# pPsch.net
KiCad netlist of a schematic drawn in Altium Designer
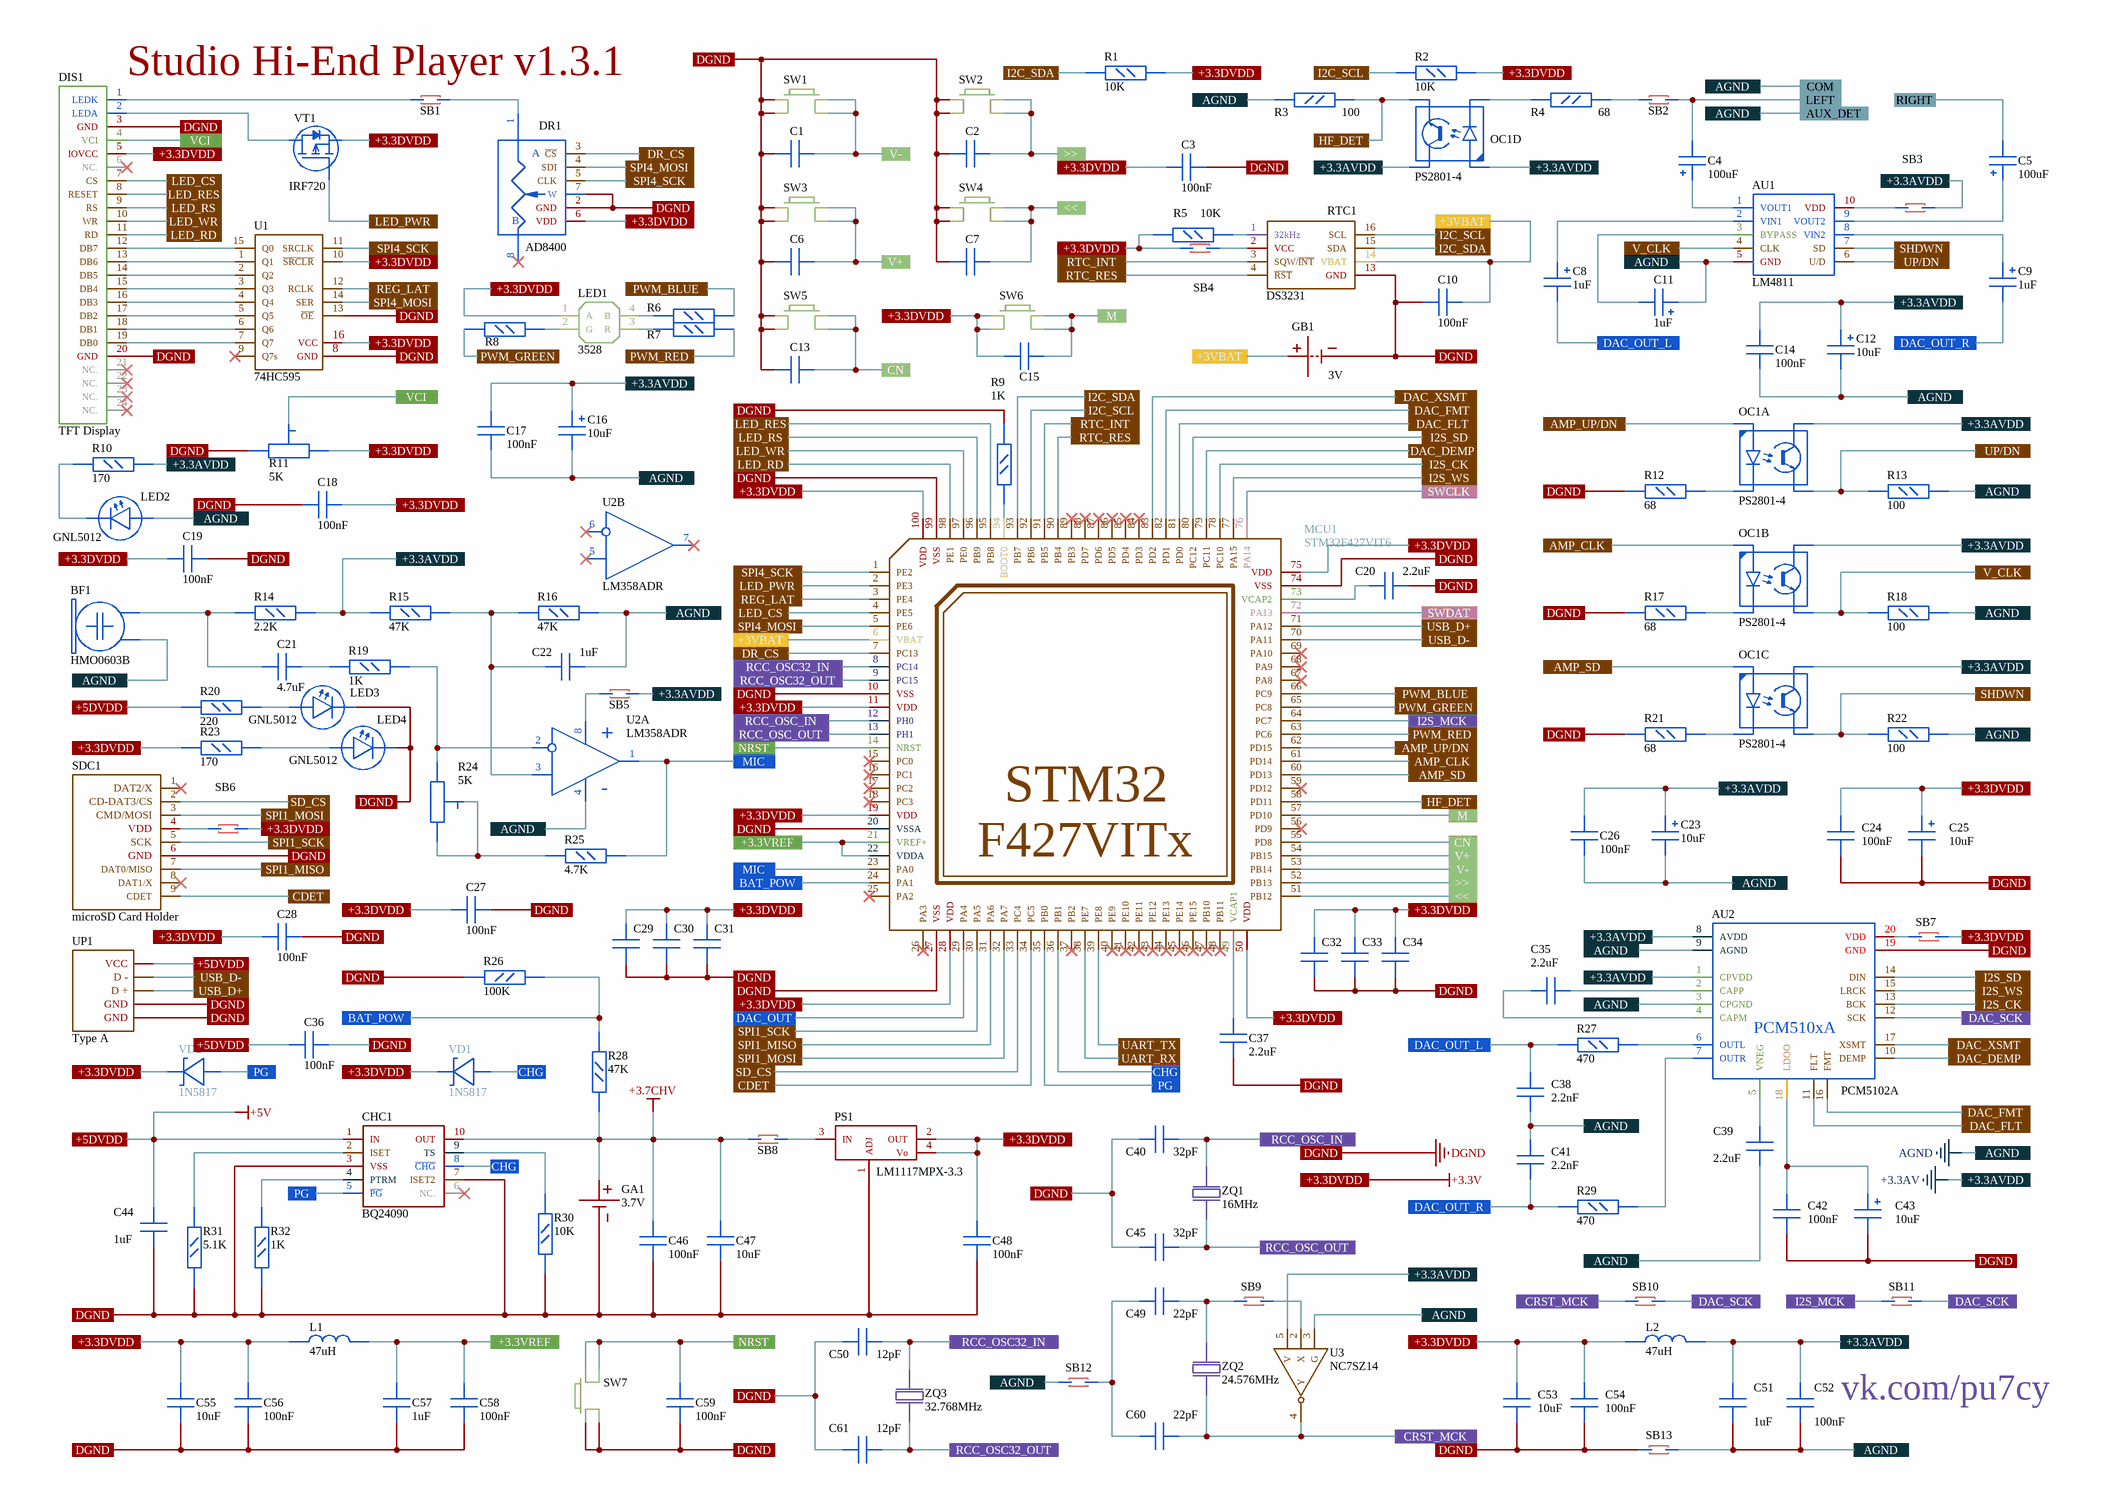
[diagram p0: pPsch.SchDoc]

(export (version "E")
  (design (tool "Eeschema 10.0.6"))
  (components
    (comp (ref "AU1")
      (value "LM4811")
      (footprint "HVSSOP10")
      (libsource (lib "AudioStonesLib_Col") (part "LM4811"))
    )
    (comp (ref "AU2")
      (value "PCM5102A")
      (footprint "TSSOP20")
      (libsource (lib "AudioStonesLib_Col") (part "PCM510xA"))
    )
    (comp (ref "BF1")
      (value "HMO0603B")
      (footprint "ACCUM")
      (libsource (lib "CustomMillLib_Col") (part "Microphone"))
    )
    (comp (ref "C1") (value "100nF") (footprint "C0603") (libsource (lib "CustomMillLib_Col") (part "Cap")))
    (comp (ref "C2") (value "100nF") (footprint "C0603") (libsource (lib "CustomMillLib_Col") (part "Cap")))
    (comp (ref "C3") (value "100nF") (footprint "C0603") (libsource (lib "CustomMillLib_Col") (part "Cap")))
    (comp (ref "C4")
      (value "100uF")
      (footprint "CAP_TAN-C")
      (libsource (lib "CustomMillLib_Col") (part "Cap_Pol"))
    )
    (comp (ref "C5")
      (value "100uF")
      (footprint "CAP_TAN-C")
      (libsource (lib "CustomMillLib_Col") (part "Cap_Pol"))
    )
    (comp (ref "C6") (value "100nF") (footprint "C0603") (libsource (lib "CustomMillLib_Col") (part "Cap")))
    (comp (ref "C7") (value "100nF") (footprint "C0603") (libsource (lib "CustomMillLib_Col") (part "Cap")))
    (comp (ref "C8")
      (value "1uF")
      (footprint "CAP_TAN-A")
      (libsource (lib "CustomMillLib_Col") (part "Cap_Pol"))
    )
    (comp (ref "C9")
      (value "1uF")
      (footprint "CAP_TAN-A")
      (libsource (lib "CustomMillLib_Col") (part "Cap_Pol"))
    )
    (comp (ref "C10") (value "100nF") (footprint "C0603") (libsource (lib "CustomMillLib_Col") (part "Cap")))
    (comp (ref "C11")
      (value "1uF")
      (footprint "CAP_TAN-A")
      (libsource (lib "CustomMillLib_Col") (part "Cap_Pol"))
    )
    (comp (ref "C12")
      (value "10uF")
      (footprint "CAP_TAN-A")
      (libsource (lib "CustomMillLib_Col") (part "Cap_Pol"))
    )
    (comp (ref "C13") (value "100nF") (footprint "C0603") (libsource (lib "CustomMillLib_Col") (part "Cap")))
    (comp (ref "C14") (value "100nF") (footprint "C0603") (libsource (lib "CustomMillLib_Col") (part "Cap")))
    (comp (ref "C15") (value "100nF") (footprint "C0603") (libsource (lib "CustomMillLib_Col") (part "Cap")))
    (comp (ref "C16")
      (value "10uF")
      (footprint "CAP_TAN-A")
      (libsource (lib "CustomMillLib_Col") (part "Cap_Pol"))
    )
    (comp (ref "C17") (value "100nF") (footprint "C0603") (libsource (lib "CustomMillLib_Col") (part "Cap")))
    (comp (ref "C18") (value "100nF") (footprint "C0603") (libsource (lib "CustomMillLib_Col") (part "Cap")))
    (comp (ref "C19") (value "100nF") (footprint "C0603") (libsource (lib "CustomMillLib_Col") (part "Cap")))
    (comp (ref "C20") (value "2.2uF") (footprint "C0805") (libsource (lib "CustomMillLib_Col") (part "Cap")))
    (comp (ref "C21") (value "4.7uF") (footprint "C0805") (libsource (lib "CustomMillLib_Col") (part "Cap")))
    (comp (ref "C22") (value "1uF") (footprint "C0805") (libsource (lib "CustomMillLib_Col") (part "Cap")))
    (comp (ref "C23")
      (value "10uF")
      (footprint "CAP_TAN-A")
      (libsource (lib "CustomMillLib_Col") (part "Cap_Pol"))
    )
    (comp (ref "C24") (value "100nF") (footprint "C0603") (libsource (lib "CustomMillLib_Col") (part "Cap")))
    (comp (ref "C25")
      (value "10uF")
      (footprint "CAP_TAN-A")
      (libsource (lib "CustomMillLib_Col") (part "Cap_Pol"))
    )
    (comp (ref "C26") (value "100nF") (footprint "C0603") (libsource (lib "CustomMillLib_Col") (part "Cap")))
    (comp (ref "C27") (value "100nF") (footprint "C0603") (libsource (lib "CustomMillLib_Col") (part "Cap")))
    (comp (ref "C28") (value "100nF") (footprint "C0603") (libsource (lib "CustomMillLib_Col") (part "Cap")))
    (comp (ref "C29") (value "100nF") (footprint "C0603") (libsource (lib "CustomMillLib_Col") (part "Cap")))
    (comp (ref "C30") (value "100nF") (footprint "C0603") (libsource (lib "CustomMillLib_Col") (part "Cap")))
    (comp (ref "C31") (value "100nF") (footprint "C0603") (libsource (lib "CustomMillLib_Col") (part "Cap")))
    (comp (ref "C32") (value "100nF") (footprint "C0603") (libsource (lib "CustomMillLib_Col") (part "Cap")))
    (comp (ref "C33") (value "100nF") (footprint "C0603") (libsource (lib "CustomMillLib_Col") (part "Cap")))
    (comp (ref "C34") (value "100nF") (footprint "C0603") (libsource (lib "CustomMillLib_Col") (part "Cap")))
    (comp (ref "C35") (value "2.2uF") (footprint "C0805") (libsource (lib "CustomMillLib_Col") (part "Cap")))
    (comp (ref "C36") (value "100nF") (footprint "C0603") (libsource (lib "CustomMillLib_Col") (part "Cap")))
    (comp (ref "C37") (value "2.2uF") (footprint "C0805") (libsource (lib "CustomMillLib_Col") (part "Cap")))
    (comp (ref "C38") (value "2.2nF") (footprint "C0603") (libsource (lib "CustomMillLib_Col") (part "Cap")))
    (comp (ref "C39") (value "2.2uF") (footprint "C0805") (libsource (lib "CustomMillLib_Col") (part "Cap")))
    (comp (ref "C40") (value "32pF") (footprint "C0402") (libsource (lib "CustomMillLib_Col") (part "Cap")))
    (comp (ref "C41") (value "2.2nF") (footprint "C0603") (libsource (lib "CustomMillLib_Col") (part "Cap")))
    (comp (ref "C42") (value "100nF") (footprint "C0603") (libsource (lib "CustomMillLib_Col") (part "Cap")))
    (comp (ref "C43")
      (value "10uF")
      (footprint "CAP_TAN-A")
      (libsource (lib "CustomMillLib_Col") (part "Cap_Pol"))
    )
    (comp (ref "C44") (value "1uF") (footprint "C0805") (libsource (lib "CustomMillLib_Col") (part "Cap")))
    (comp (ref "C45") (value "32pF") (footprint "C0402") (libsource (lib "CustomMillLib_Col") (part "Cap")))
    (comp (ref "C46") (value "100nF") (footprint "C0603") (libsource (lib "CustomMillLib_Col") (part "Cap")))
    (comp (ref "C47") (value "10uF") (footprint "C0805") (libsource (lib "CustomMillLib_Col") (part "Cap")))
    (comp (ref "C48") (value "100nF") (footprint "C0603") (libsource (lib "CustomMillLib_Col") (part "Cap")))
    (comp (ref "C49") (value "22pF") (footprint "C0402") (libsource (lib "CustomMillLib_Col") (part "Cap")))
    (comp (ref "C50") (value "12pF") (footprint "C0402") (libsource (lib "CustomMillLib_Col") (part "Cap")))
    (comp (ref "C51") (value "1uF") (footprint "C0805") (libsource (lib "CustomMillLib_Col") (part "Cap")))
    (comp (ref "C52") (value "100nF") (footprint "C0603") (libsource (lib "CustomMillLib_Col") (part "Cap")))
    (comp (ref "C53") (value "10uF") (footprint "C0805") (libsource (lib "CustomMillLib_Col") (part "Cap")))
    (comp (ref "C54") (value "100nF") (footprint "C0603") (libsource (lib "CustomMillLib_Col") (part "Cap")))
    (comp (ref "C55") (value "10uF") (footprint "C0805") (libsource (lib "CustomMillLib_Col") (part "Cap")))
    (comp (ref "C56") (value "100nF") (footprint "C0603") (libsource (lib "CustomMillLib_Col") (part "Cap")))
    (comp (ref "C57") (value "1uF") (footprint "C0805") (libsource (lib "CustomMillLib_Col") (part "Cap")))
    (comp (ref "C58") (value "100nF") (footprint "C0603") (libsource (lib "CustomMillLib_Col") (part "Cap")))
    (comp (ref "C59") (value "100nF") (footprint "C0603") (libsource (lib "CustomMillLib_Col") (part "Cap")))
    (comp (ref "C60") (value "22pF") (footprint "C0402") (libsource (lib "CustomMillLib_Col") (part "Cap")))
    (comp (ref "C61") (value "12pF") (footprint "C0402") (libsource (lib "CustomMillLib_Col") (part "Cap")))
    (comp (ref "CHC1")
      (value "BQ24090")
      (footprint "HVSSOP10")
      (libsource (lib "PowerSupplies_Col") (part "BQ24090"))
    )
    (comp (ref "DIS1")
      (value "TFT Display")
      (footprint "FPC-24")
      (libsource (lib "OtherEquipmentLib_Col") (part "TFT RGB (ST7789/ILI9341)"))
    )
    (comp (ref "DR1")
      (value "AD8400")
      (footprint "SOIC8")
      (libsource (lib "DigitalUnits_Col") (part "AD8400"))
    )
    (comp (ref "GA1")
      (value "3.7V")
      (footprint "ACCUM")
      (libsource (lib "PowerSupplies_Col") (part "Accumulator"))
    )
    (comp (ref "GB1")
      (value "3V")
      (footprint "CR1616-SMD")
      (libsource (lib "PowerSupplies_Col") (part "Battery"))
    )
    (comp (ref "L1")
      (value "47uH")
      (footprint "L0805")
      (libsource (lib "CustomMillLib_Col") (part "Inductor"))
    )
    (comp (ref "L2")
      (value "47uH")
      (footprint "L0805")
      (libsource (lib "CustomMillLib_Col") (part "Inductor"))
    )
    (comp (ref "LED1")
      (value "3528")
      (footprint "LED-3528")
      (libsource (lib "CustomMillLib_Col") (part "LED-RGB"))
    )
    (comp (ref "LED2")
      (value "GNL5012")
      (footprint "LED0603")
      (libsource (lib "CustomMillLib_Col") (part "LED"))
    )
    (comp (ref "LED3")
      (value "GNL5012")
      (footprint "LED0603")
      (libsource (lib "CustomMillLib_Col") (part "LED"))
    )
    (comp (ref "LED4")
      (value "GNL5012")
      (footprint "LED0603")
      (libsource (lib "CustomMillLib_Col") (part "LED"))
    )
    (comp (ref "MCU1")
      (value "STM32F427VIT6")
      (footprint "LQFP100")
      (libsource (lib "STM32Lib_Col") (part "STM32F427VITx"))
    )
    (comp (ref "OC1")
      (value "PS2801-4")
      (footprint "SSOP16")
      (libsource (lib "CustomMillLib_Col") (part "PS2801-4"))
    )
    (comp (ref "PS1")
      (value "LM1117MPX-3.3")
      (footprint "SOT-223")
      (libsource (lib "PowerSupplies_Col") (part "LM1117"))
    )
    (comp (ref "R1") (value "10K") (footprint "R0603") (libsource (lib "CustomMillLib_Col") (part "Res")))
    (comp (ref "R2") (value "10K") (footprint "R0603") (libsource (lib "CustomMillLib_Col") (part "Res")))
    (comp (ref "R3") (value "100") (footprint "R0805") (libsource (lib "CustomMillLib_Col") (part "Res")))
    (comp (ref "R4") (value "68") (footprint "R0805") (libsource (lib "CustomMillLib_Col") (part "Res")))
    (comp (ref "R5") (value "10K") (footprint "R0603") (libsource (lib "CustomMillLib_Col") (part "Res")))
    (comp (ref "R6") (value "220") (footprint "R0603") (libsource (lib "CustomMillLib_Col") (part "Res")))
    (comp (ref "R7") (value "220") (footprint "R0603") (libsource (lib "CustomMillLib_Col") (part "Res")))
    (comp (ref "R8") (value "220") (footprint "R0603") (libsource (lib "CustomMillLib_Col") (part "Res")))
    (comp (ref "R9") (value "1K") (footprint "R0603") (libsource (lib "CustomMillLib_Col") (part "Res")))
    (comp (ref "R10") (value "170") (footprint "R0805") (libsource (lib "CustomMillLib_Col") (part "Res")))
    (comp (ref "R11") (value "5K") (footprint "EVM3") (libsource (lib "") (part "Res Adj_1")))
    (comp (ref "R12") (value "68") (footprint "R0805") (libsource (lib "CustomMillLib_Col") (part "Res")))
    (comp (ref "R13") (value "100") (footprint "R0805") (libsource (lib "CustomMillLib_Col") (part "Res")))
    (comp (ref "R14") (value "2.2K") (footprint "R0603") (libsource (lib "CustomMillLib_Col") (part "Res")))
    (comp (ref "R15") (value "47K") (footprint "R0603") (libsource (lib "CustomMillLib_Col") (part "Res")))
    (comp (ref "R16") (value "47K") (footprint "R0603") (libsource (lib "CustomMillLib_Col") (part "Res")))
    (comp (ref "R17") (value "68") (footprint "R0805") (libsource (lib "CustomMillLib_Col") (part "Res")))
    (comp (ref "R18") (value "100") (footprint "R0805") (libsource (lib "CustomMillLib_Col") (part "Res")))
    (comp (ref "R19") (value "1K") (footprint "R0603") (libsource (lib "CustomMillLib_Col") (part "Res")))
    (comp (ref "R20") (value "220") (footprint "R0805") (libsource (lib "CustomMillLib_Col") (part "Res")))
    (comp (ref "R21") (value "68") (footprint "R0805") (libsource (lib "CustomMillLib_Col") (part "Res")))
    (comp (ref "R22") (value "100") (footprint "R0805") (libsource (lib "CustomMillLib_Col") (part "Res")))
    (comp (ref "R23") (value "170") (footprint "R0805") (libsource (lib "CustomMillLib_Col") (part "Res")))
    (comp (ref "R24") (value "5K") (footprint "EVM3") (libsource (lib "CustomMillLib_Col") (part "Res Adj")))
    (comp (ref "R25") (value "4.7K") (footprint "R0603") (libsource (lib "CustomMillLib_Col") (part "Res")))
    (comp (ref "R26") (value "100K") (footprint "R0603") (libsource (lib "CustomMillLib_Col") (part "Res")))
    (comp (ref "R27") (value "470") (footprint "R0603") (libsource (lib "CustomMillLib_Col") (part "Res")))
    (comp (ref "R28") (value "47K") (footprint "R0603") (libsource (lib "CustomMillLib_Col") (part "Res")))
    (comp (ref "R29") (value "470") (footprint "R0603") (libsource (lib "CustomMillLib_Col") (part "Res")))
    (comp (ref "R30") (value "10K") (footprint "R0603") (libsource (lib "CustomMillLib_Col") (part "Res")))
    (comp (ref "R31") (value "5.1K") (footprint "R0603") (libsource (lib "CustomMillLib_Col") (part "Res")))
    (comp (ref "R32") (value "1K") (footprint "R0603") (libsource (lib "CustomMillLib_Col") (part "Res")))
    (comp (ref "RTC1")
      (value "DS3231")
      (footprint "SOP16")
      (libsource (lib "DigitalUnits_Col") (part "DS3231"))
    )
    (comp (ref "SB1")
      (value "Soldier Bridge")
      (footprint "SOLDBR")
      (libsource (lib "CustomMillLib_Col") (part "Soldier Bridge"))
    )
    (comp (ref "SB2")
      (value "Soldier Bridge")
      (footprint "SOLDBR")
      (libsource (lib "CustomMillLib_Col") (part "Soldier Bridge"))
    )
    (comp (ref "SB3")
      (value "Soldier Bridge")
      (footprint "SOLDBR")
      (libsource (lib "CustomMillLib_Col") (part "Soldier Bridge"))
    )
    (comp (ref "SB4")
      (value "Soldier Bridge")
      (footprint "SOLDBR")
      (libsource (lib "CustomMillLib_Col") (part "Soldier Bridge"))
    )
    (comp (ref "SB5")
      (value "Soldier Bridge")
      (footprint "SOLDBR")
      (libsource (lib "CustomMillLib_Col") (part "Soldier Bridge"))
    )
    (comp (ref "SB6")
      (value "Soldier Bridge")
      (footprint "SOLDBR")
      (libsource (lib "CustomMillLib_Col") (part "Soldier Bridge"))
    )
    (comp (ref "SB7")
      (value "Soldier Bridge")
      (footprint "SOLDBR")
      (libsource (lib "CustomMillLib_Col") (part "Soldier Bridge"))
    )
    (comp (ref "SB8")
      (value "Soldier Bridge")
      (footprint "SOLDBR")
      (libsource (lib "CustomMillLib_Col") (part "Soldier Bridge"))
    )
    (comp (ref "SB9")
      (value "Soldier Bridge")
      (footprint "SOLDBR")
      (libsource (lib "CustomMillLib_Col") (part "Soldier Bridge"))
    )
    (comp (ref "SB10")
      (value "Soldier Bridge")
      (footprint "SOLDBR")
      (libsource (lib "CustomMillLib_Col") (part "Soldier Bridge"))
    )
    (comp (ref "SB11")
      (value "Soldier Bridge")
      (footprint "SOLDBR")
      (libsource (lib "CustomMillLib_Col") (part "Soldier Bridge"))
    )
    (comp (ref "SB12")
      (value "Soldier Bridge")
      (footprint "SOLDBR")
      (libsource (lib "CustomMillLib_Col") (part "Soldier Bridge"))
    )
    (comp (ref "SB13")
      (value "Soldier Bridge")
      (footprint "SOLDBR")
      (libsource (lib "CustomMillLib_Col") (part "Soldier Bridge"))
    )
    (comp (ref "SDC1")
      (value "microSD Card Holder")
      (footprint "SDCARD-MICRO")
      (libsource (lib "OtherEquipmentLib_Col") (part "SPI_Card_Reader"))
    )
    (comp (ref "SW1")
      (value "KLS7-TS6601")
      (footprint "BUT-SMD-6X6-8X6.2")
      (libsource (lib "CustomMillLib_Col") (part "Button_2"))
    )
    (comp (ref "SW2")
      (value "KLS7-TS6601")
      (footprint "BUT-SMD-6X6-8X6.2")
      (libsource (lib "CustomMillLib_Col") (part "Button_2"))
    )
    (comp (ref "SW3")
      (value "KLS7-TS6601")
      (footprint "BUT-SMD-6X6-8X6.2")
      (libsource (lib "CustomMillLib_Col") (part "Button_2"))
    )
    (comp (ref "SW4")
      (value "KLS7-TS6601")
      (footprint "BUT-SMD-6X6-8X6.2")
      (libsource (lib "CustomMillLib_Col") (part "Button_2"))
    )
    (comp (ref "SW5")
      (value "KLS7-TS6601")
      (footprint "BUT-SMD-6X6-8X6.2")
      (libsource (lib "CustomMillLib_Col") (part "Button_2"))
    )
    (comp (ref "SW6")
      (value "KLS7-TS6601")
      (footprint "BUT-SMD-3X4-C")
      (libsource (lib "CustomMillLib_Col") (part "Button_2"))
    )
    (comp (ref "SW7")
      (value "KLS7-TS6601")
      (footprint "BUT-SMD-6X6-8X6.2")
      (libsource (lib "CustomMillLib_Col") (part "Button_2"))
    )
    (comp (ref "U1")
      (value "74HC595")
      (footprint "TSSOP16")
      (libsource (lib "DigitalUnits_Col") (part "74HC595 (REG)"))
    )
    (comp (ref "U2")
      (value "LM358ADR")
      (footprint "SOIC8")
      (libsource (lib "CustomMillLib_Col") (part "LM358"))
    )
    (comp (ref "U3")
      (value "NC7SZ14")
      (footprint "SOT23-5")
      (libsource (lib "DigitalUnits_Col") (part "NOT"))
    )
    (comp (ref "UP1")
      (value "Type A")
      (footprint "USB-MICRO-F")
      (libsource (lib "OtherEquipmentLib_Col") (part "USB"))
    )
    (comp (ref "VD1")
      (value "1N5817")
      (footprint "AXIAL10D-TR")
      (libsource (lib "CustomMillLib_Col") (part "Schottky"))
    )
    (comp (ref "VD2")
      (value "1N5817")
      (footprint "AXIAL10D-TR")
      (libsource (lib "CustomMillLib_Col") (part "Schottky"))
    )
    (comp (ref "VT1")
      (value "IRF720")
      (footprint "TO-220V")
      (libsource (lib "CustomMillLib_Col") (part "MOSFET-P"))
    )
    (comp (ref "ZQ1")
      (value "16MHz")
      (footprint "CRYSTALL-SMD")
      (libsource (lib "CustomMillLib_Col") (part "Crystall"))
    )
    (comp (ref "ZQ2")
      (value "24.576MHz")
      (footprint "HC-49")
      (libsource (lib "CustomMillLib_Col") (part "Crystall"))
    )
    (comp (ref "ZQ3")
      (value "32.768MHz")
      (footprint "NX3215SA")
      (libsource (lib "CustomMillLib_Col") (part "Crystall"))
    )
  )
  (nets
    (net (code "1") (name "+3.3AV") (class "Default")
      (node (ref "AU2") (pin "1") (pinfunction "CPVDD_1") (pintype "passive"))
      (node (ref "AU2") (pin "8") (pinfunction "AVDD_8") (pintype "passive"))
      (node (ref "C12") (pin "1") (pinfunction "61_1") (pintype "passive"))
      (node (ref "C14") (pin "2") (pinfunction "62_2") (pintype "passive"))
      (node (ref "C16") (pin "1") (pinfunction "61_1") (pintype "passive"))
      (node (ref "C17") (pin "2") (pinfunction "62_2") (pintype "passive"))
      (node (ref "C23") (pin "1") (pinfunction "61_1") (pintype "passive"))
      (node (ref "C26") (pin "2") (pinfunction "62_2") (pintype "passive"))
      (node (ref "C51") (pin "2") (pinfunction "62_2") (pintype "passive"))
      (node (ref "C52") (pin "2") (pinfunction "62_2") (pintype "passive"))
      (node (ref "L2") (pin "2") (pinfunction "4_2") (pintype "passive"))
      (node (ref "OC1") (pin "10") (pinfunction "4_10") (pintype "passive"))
      (node (ref "OC1") (pin "12") (pinfunction "4_12") (pintype "passive"))
      (node (ref "OC1") (pin "14") (pinfunction "4_14") (pintype "passive"))
      (node (ref "OC1") (pin "16") (pinfunction "4_16") (pintype "passive"))
      (node (ref "OC1") (pin "7") (pinfunction "1_7") (pintype "passive"))
      (node (ref "R10") (pin "2") (pinfunction "2_2") (pintype "passive"))
      (node (ref "R14") (pin "2") (pinfunction "2_2") (pintype "passive"))
      (node (ref "R15") (pin "2") (pinfunction "2_2") (pintype "passive"))
      (node (ref "SB3") (pin "2") (pintype "passive"))
      (node (ref "SB5") (pin "2") (pintype "passive"))
      (node (ref "U3") (pin "5") (pinfunction "V_5") (pintype "passive"))
    )
    (net (code "2") (name "+3.3V") (class "Default")
      (node (ref "C15") (pin "1") (pinfunction "61_1") (pintype "passive"))
      (node (ref "C18") (pin "1") (pinfunction "61_1") (pintype "passive"))
      (node (ref "C19") (pin "1") (pinfunction "61_1") (pintype "passive"))
      (node (ref "C24") (pin "2") (pinfunction "62_2") (pintype "passive"))
      (node (ref "C25") (pin "1") (pinfunction "61_1") (pintype "passive"))
      (node (ref "C27") (pin "1") (pinfunction "61_1") (pintype "passive"))
      (node (ref "C28") (pin "1") (pinfunction "61_1") (pintype "passive"))
      (node (ref "C29") (pin "2") (pinfunction "62_2") (pintype "passive"))
      (node (ref "C3") (pin "1") (pinfunction "61_1") (pintype "passive"))
      (node (ref "C30") (pin "2") (pinfunction "62_2") (pintype "passive"))
      (node (ref "C31") (pin "2") (pinfunction "62_2") (pintype "passive"))
      (node (ref "C32") (pin "2") (pinfunction "62_2") (pintype "passive"))
      (node (ref "C33") (pin "2") (pinfunction "62_2") (pintype "passive"))
      (node (ref "C34") (pin "2") (pinfunction "62_2") (pintype "passive"))
      (node (ref "C48") (pin "2") (pinfunction "62_2") (pintype "passive"))
      (node (ref "C53") (pin "2") (pinfunction "62_2") (pintype "passive"))
      (node (ref "C54") (pin "2") (pinfunction "62_2") (pintype "passive"))
      (node (ref "C55") (pin "2") (pinfunction "62_2") (pintype "passive"))
      (node (ref "C56") (pin "2") (pinfunction "62_2") (pintype "passive"))
      (node (ref "DIS1") (pin "5") (pinfunction "IOVCC_5") (pintype "passive"))
      (node (ref "DR1") (pin "6") (pinfunction "VDD_6") (pintype "passive"))
      (node (ref "L1") (pin "1") (pinfunction "3_1") (pintype "passive"))
      (node (ref "L2") (pin "1") (pinfunction "3_1") (pintype "passive"))
      (node (ref "LED1") (pin "1") (pinfunction "A_1") (pintype "passive"))
      (node (ref "MCU1") (pin "100") (pinfunction "VDD_100") (pintype "passive"))
      (node (ref "MCU1") (pin "11") (pinfunction "VDD_11") (pintype "passive"))
      (node (ref "MCU1") (pin "19") (pinfunction "VDD_19") (pintype "passive"))
      (node (ref "MCU1") (pin "28") (pinfunction "VDD_28") (pintype "passive"))
      (node (ref "MCU1") (pin "50") (pinfunction "VDD_50") (pintype "passive"))
      (node (ref "MCU1") (pin "75") (pinfunction "VDD_75") (pintype "passive"))
      (node (ref "PS1") (pin "2") (pinfunction "OUT_2") (pintype "passive"))
      (node (ref "PS1") (pin "4") (pinfunction "Vo_4") (pintype "passive"))
      (node (ref "R1") (pin "2") (pinfunction "2_2") (pintype "passive"))
      (node (ref "R11") (pin "3") (pinfunction "3_3") (pintype "passive"))
      (node (ref "R2") (pin "2") (pinfunction "2_2") (pintype "passive"))
      (node (ref "R23") (pin "1") (pinfunction "2_1") (pintype "passive"))
      (node (ref "R5") (pin "1") (pinfunction "2_1") (pintype "passive"))
      (node (ref "SB4") (pin "1") (pintype "passive"))
      (node (ref "SB6") (pin "2") (pintype "passive"))
      (node (ref "SB7") (pin "2") (pintype "passive"))
      (node (ref "SW6") (pin "1") (pinfunction "Q1_1") (pintype "passive"))
      (node (ref "SW6") (pin "2") (pinfunction "Q1_2") (pintype "passive"))
      (node (ref "U1") (pin "10") (pinfunction "SRCLR_10") (pintype "passive"))
      (node (ref "U1") (pin "16") (pinfunction "VCC_16") (pintype "passive"))
      (node (ref "VD1") (pin "2") (pinfunction "64_2") (pintype "passive"))
      (node (ref "VD2") (pin "2") (pinfunction "64_2") (pintype "passive"))
      (node (ref "VT1") (pin "3") (pinfunction "S_3") (pintype "passive"))
    )
    (net (code "3") (name "+3.7CHV") (class "Default")
      (node (ref "C46") (pin "2") (pinfunction "62_2") (pintype "passive"))
      (node (ref "C47") (pin "2") (pinfunction "62_2") (pintype "passive"))
      (node (ref "CHC1") (pin "10") (pinfunction "OUT_10") (pintype "passive"))
      (node (ref "GA1") (pin "1") (pintype "passive"))
      (node (ref "R28") (pin "2") (pinfunction "2_2") (pintype "passive"))
      (node (ref "SB8") (pin "1") (pintype "passive"))
    )
    (net (code "4") (name "+5V") (class "Default")
      (node (ref "C36") (pin "1") (pinfunction "61_1") (pintype "passive"))
      (node (ref "C44") (pin "2") (pinfunction "62_2") (pintype "passive"))
      (node (ref "CHC1") (pin "1") (pinfunction "IN_1") (pintype "passive"))
      (node (ref "R20") (pin "1") (pinfunction "2_1") (pintype "passive"))
      (node (ref "UP1") (pin "1") (pinfunction "VCC_1") (pintype "passive"))
    )
    (net (code "5") (name "/+3.3VREF") (class "Default")
      (node (ref "C57") (pin "2") (pinfunction "62_2") (pintype "passive"))
      (node (ref "C58") (pin "2") (pinfunction "62_2") (pintype "passive"))
      (node (ref "L1") (pin "2") (pinfunction "4_2") (pintype "passive"))
      (node (ref "MCU1") (pin "21") (pinfunction "VREF+_21") (pintype "passive"))
      (node (ref "MCU1") (pin "22") (pinfunction "VDDA_22") (pintype "passive"))
    )
    (net (code "6") (name "/+3VBAT") (class "Default")
      (node (ref "C10") (pin "2") (pinfunction "62_2") (pintype "passive"))
      (node (ref "GB1") (pin "2") (pintype "passive"))
      (node (ref "MCU1") (pin "6") (pinfunction "VBAT_6") (pintype "passive"))
      (node (ref "RTC1") (pin "14") (pinfunction "VBAT_14") (pintype "passive"))
    )
    (net (code "7") (name "/<<") (class "Default")
      (node (ref "C7") (pin "1") (pinfunction "61_1") (pintype "passive"))
      (node (ref "MCU1") (pin "51") (pinfunction "PB12_51") (pintype "passive"))
      (node (ref "SW4") (pin "3") (pinfunction "Q2_3") (pintype "passive"))
      (node (ref "SW4") (pin "4") (pinfunction "Q2_4") (pintype "passive"))
    )
    (net (code "8") (name "/>>") (class "Default")
      (node (ref "C2") (pin "1") (pinfunction "61_1") (pintype "passive"))
      (node (ref "MCU1") (pin "52") (pinfunction "PB13_52") (pintype "passive"))
      (node (ref "SW2") (pin "3") (pinfunction "Q2_3") (pintype "passive"))
      (node (ref "SW2") (pin "4") (pinfunction "Q2_4") (pintype "passive"))
    )
    (net (code "9") (name "/AMP_CLK") (class "Default")
      (node (ref "MCU1") (pin "61") (pinfunction "PD14_61") (pintype "passive"))
      (node (ref "OC1") (pin "3") (pinfunction "1_3") (pintype "passive"))
    )
    (net (code "10") (name "/AMP_SD") (class "Default")
      (node (ref "MCU1") (pin "60") (pinfunction "PD13_60") (pintype "passive"))
      (node (ref "OC1") (pin "5") (pinfunction "1_5") (pintype "passive"))
    )
    (net (code "11") (name "/AMP_UP{slash}DN") (class "Default")
      (node (ref "MCU1") (pin "62") (pinfunction "PD15_62") (pintype "passive"))
      (node (ref "OC1") (pin "1") (pinfunction "1_1") (pintype "passive"))
    )
    (net (code "12") (name "/BAT_POW") (class "Default")
      (node (ref "MCU1") (pin "24") (pinfunction "PA1_24") (pintype "passive"))
      (node (ref "R26") (pin "2") (pinfunction "2_2") (pintype "passive"))
      (node (ref "R28") (pin "1") (pinfunction "2_1") (pintype "passive"))
    )
    (net (code "13") (name "/CDET") (class "Default")
      (node (ref "MCU1") (pin "34") (pinfunction "PC5_34") (pintype "passive"))
      (node (ref "SDC1") (pin "9") (pinfunction "CDET_9") (pintype "passive"))
    )
    (net (code "14") (name "/CHG") (class "Default")
      (node (ref "CHC1") (pin "8") (pinfunction "CHG_8") (pintype "passive"))
      (node (ref "MCU1") (pin "36") (pinfunction "PB1_36") (pintype "passive"))
      (node (ref "VD1") (pin "1") (pinfunction "63_1") (pintype "passive"))
    )
    (net (code "15") (name "/CN") (class "Default")
      (node (ref "C13") (pin "1") (pinfunction "61_1") (pintype "passive"))
      (node (ref "MCU1") (pin "55") (pinfunction "PD8_55") (pintype "passive"))
      (node (ref "SW5") (pin "3") (pinfunction "Q2_3") (pintype "passive"))
      (node (ref "SW5") (pin "4") (pinfunction "Q2_4") (pintype "passive"))
    )
    (net (code "16") (name "/CRST_MCK") (class "Default")
      (node (ref "C60") (pin "1") (pinfunction "61_1") (pintype "passive"))
      (node (ref "SB10") (pin "1") (pintype "passive"))
      (node (ref "U3") (pin "4") (pinfunction "Y_4") (pintype "passive"))
      (node (ref "ZQ2") (pin "2") (pinfunction "2_2") (pintype "passive"))
    )
    (net (code "17") (name "/DAC_DEMP") (class "Default")
      (node (ref "AU2") (pin "10") (pinfunction "DEMP_10") (pintype "passive"))
      (node (ref "MCU1") (pin "79") (pinfunction "PC11_79") (pintype "passive"))
    )
    (net (code "18") (name "/DAC_FLT") (class "Default")
      (node (ref "AU2") (pin "11") (pinfunction "FLT_11") (pintype "passive"))
      (node (ref "MCU1") (pin "81") (pinfunction "PD0_81") (pintype "passive"))
    )
    (net (code "19") (name "/DAC_FMT") (class "Default")
      (node (ref "AU2") (pin "16") (pinfunction "FMT_16") (pintype "passive"))
      (node (ref "MCU1") (pin "82") (pinfunction "PD1_82") (pintype "passive"))
    )
    (net (code "20") (name "/DAC_OUT") (class "Default")
      (node (ref "MCU1") (pin "29") (pinfunction "PA4_29") (pintype "passive"))
    )
    (net (code "21") (name "/DAC_OUT_L") (class "Default")
      (node (ref "C38") (pin "2") (pinfunction "62_2") (pintype "passive"))
      (node (ref "C8") (pin "2") (pinfunction "62_2") (pintype "passive"))
      (node (ref "R27") (pin "1") (pinfunction "2_1") (pintype "passive"))
    )
    (net (code "22") (name "/DAC_OUT_R") (class "Default")
      (node (ref "C41") (pin "1") (pinfunction "61_1") (pintype "passive"))
      (node (ref "C9") (pin "2") (pinfunction "62_2") (pintype "passive"))
      (node (ref "R29") (pin "1") (pinfunction "2_1") (pintype "passive"))
    )
    (net (code "23") (name "/DAC_SCK") (class "Default")
      (node (ref "AU2") (pin "12") (pinfunction "SCK_12") (pintype "passive"))
      (node (ref "SB10") (pin "2") (pintype "passive"))
      (node (ref "SB11") (pin "2") (pintype "passive"))
    )
    (net (code "24") (name "/DAC_XSMT") (class "Default")
      (node (ref "AU2") (pin "17") (pinfunction "XSMT_17") (pintype "passive"))
      (node (ref "MCU1") (pin "83") (pinfunction "PD2_83") (pintype "passive"))
    )
    (net (code "25") (name "/DR_CS") (class "Default")
      (node (ref "DR1") (pin "3") (pinfunction "CS_3") (pintype "passive"))
      (node (ref "MCU1") (pin "7") (pinfunction "PC13_7") (pintype "passive"))
    )
    (net (code "26") (name "/HF_DET") (class "Default")
      (node (ref "MCU1") (pin "58") (pinfunction "PD11_58") (pintype "passive"))
      (node (ref "OC1") (pin "9") (pinfunction "3_9") (pintype "passive"))
      (node (ref "R3") (pin "1") (pinfunction "2_1") (pintype "passive"))
    )
    (net (code "27") (name "/I2C_SCL") (class "Default")
      (node (ref "MCU1") (pin "92") (pinfunction "PB6_92") (pintype "passive"))
      (node (ref "R2") (pin "1") (pinfunction "2_1") (pintype "passive"))
      (node (ref "RTC1") (pin "16") (pinfunction "SCL_16") (pintype "passive"))
    )
    (net (code "28") (name "/I2C_SDA") (class "Default")
      (node (ref "MCU1") (pin "93") (pinfunction "PB7_93") (pintype "passive"))
      (node (ref "R1") (pin "1") (pinfunction "2_1") (pintype "passive"))
      (node (ref "RTC1") (pin "15") (pinfunction "SDA_15") (pintype "passive"))
    )
    (net (code "29") (name "/I2S_CK") (class "Default")
      (node (ref "AU2") (pin "13") (pinfunction "BCK_13") (pintype "passive"))
      (node (ref "MCU1") (pin "78") (pinfunction "PC10_78") (pintype "passive"))
    )
    (net (code "30") (name "/I2S_MCK") (class "Default")
      (node (ref "MCU1") (pin "64") (pinfunction "PC7_64") (pintype "passive"))
      (node (ref "SB11") (pin "1") (pintype "passive"))
    )
    (net (code "31") (name "/I2S_SD") (class "Default")
      (node (ref "AU2") (pin "14") (pinfunction "DIN_14") (pintype "passive"))
      (node (ref "MCU1") (pin "80") (pinfunction "PC12_80") (pintype "passive"))
    )
    (net (code "32") (name "/I2S_WS") (class "Default")
      (node (ref "AU2") (pin "15") (pinfunction "LRCK_15") (pintype "passive"))
      (node (ref "MCU1") (pin "77") (pinfunction "PA15_77") (pintype "passive"))
    )
    (net (code "33") (name "/LED_CS") (class "Default")
      (node (ref "DIS1") (pin "7") (pinfunction "CS_7") (pintype "passive"))
      (node (ref "MCU1") (pin "4") (pinfunction "PE5_4") (pintype "passive"))
    )
    (net (code "34") (name "/LED_PWR") (class "Default")
      (node (ref "MCU1") (pin "2") (pinfunction "PE3_2") (pintype "passive"))
      (node (ref "VT1") (pin "1") (pinfunction "G_1") (pintype "passive"))
    )
    (net (code "35") (name "/LED_RD") (class "Default")
      (node (ref "DIS1") (pin "11") (pinfunction "RD_11") (pintype "passive"))
      (node (ref "MCU1") (pin "98") (pinfunction "PE1_98") (pintype "passive"))
    )
    (net (code "36") (name "/LED_RES") (class "Default")
      (node (ref "DIS1") (pin "8") (pinfunction "RESET_8") (pintype "passive"))
      (node (ref "MCU1") (pin "95") (pinfunction "PB8_95") (pintype "passive"))
    )
    (net (code "37") (name "/LED_RS") (class "Default")
      (node (ref "DIS1") (pin "9") (pinfunction "RS_9") (pintype "passive"))
      (node (ref "MCU1") (pin "96") (pinfunction "PB9_96") (pintype "passive"))
    )
    (net (code "38") (name "/LED_WR") (class "Default")
      (node (ref "DIS1") (pin "10") (pinfunction "WR_10") (pintype "passive"))
      (node (ref "MCU1") (pin "97") (pinfunction "PE0_97") (pintype "passive"))
    )
    (net (code "39") (name "/LEFT") (class "Default")
      (node (ref "C4") (pin "2") (pinfunction "62_2") (pintype "passive"))
      (node (ref "SB2") (pin "2") (pintype "passive"))
    )
    (net (code "40") (name "/M") (class "Default")
      (node (ref "C15") (pin "2") (pinfunction "62_2") (pintype "passive"))
      (node (ref "MCU1") (pin "57") (pinfunction "PD10_57") (pintype "passive"))
      (node (ref "SW6") (pin "3") (pinfunction "Q2_3") (pintype "passive"))
      (node (ref "SW6") (pin "4") (pinfunction "Q2_4") (pintype "passive"))
    )
    (net (code "41") (name "/MIC") (class "Default")
      (node (ref "MCU1") (pin "23") (pinfunction "PA0_23") (pintype "passive"))
      (node (ref "R25") (pin "2") (pinfunction "2_2") (pintype "passive"))
      (node (ref "U2") (pin "1") (pintype "passive"))
    )
    (net (code "42") (name "/NRST") (class "Default")
      (node (ref "C59") (pin "2") (pinfunction "62_2") (pintype "passive"))
      (node (ref "MCU1") (pin "14") (pinfunction "NRST_14") (pintype "passive"))
      (node (ref "SW7") (pin "3") (pinfunction "Q2_3") (pintype "passive"))
      (node (ref "SW7") (pin "4") (pinfunction "Q2_4") (pintype "passive"))
    )
    (net (code "43") (name "/PG") (class "Default")
      (node (ref "CHC1") (pin "5") (pinfunction "PG_5") (pintype "passive"))
      (node (ref "MCU1") (pin "35") (pinfunction "PB0_35") (pintype "passive"))
      (node (ref "VD2") (pin "1") (pinfunction "63_1") (pintype "passive"))
    )
    (net (code "44") (name "/PWM_BLUE") (class "Default")
      (node (ref "MCU1") (pin "66") (pinfunction "PC9_66") (pintype "passive"))
      (node (ref "R6") (pin "2") (pinfunction "2_2") (pintype "passive"))
    )
    (net (code "45") (name "/PWM_GREEN") (class "Default")
      (node (ref "MCU1") (pin "65") (pinfunction "PC8_65") (pintype "passive"))
      (node (ref "R8") (pin "1") (pinfunction "2_1") (pintype "passive"))
    )
    (net (code "46") (name "/PWM_RED") (class "Default")
      (node (ref "MCU1") (pin "63") (pinfunction "PC6_63") (pintype "passive"))
      (node (ref "R7") (pin "2") (pinfunction "2_2") (pintype "passive"))
    )
    (net (code "47") (name "/RCC_OSC32_IN") (class "Default")
      (node (ref "C50") (pin "1") (pinfunction "61_1") (pintype "passive"))
      (node (ref "MCU1") (pin "8") (pinfunction "PC14_8") (pintype "passive"))
      (node (ref "ZQ3") (pin "1") (pinfunction "10_1") (pintype "passive"))
    )
    (net (code "48") (name "/RCC_OSC32_OUT") (class "Default")
      (node (ref "C61") (pin "1") (pinfunction "61_1") (pintype "passive"))
      (node (ref "MCU1") (pin "9") (pinfunction "PC15_9") (pintype "passive"))
      (node (ref "ZQ3") (pin "2") (pinfunction "2_2") (pintype "passive"))
    )
    (net (code "49") (name "/RCC_OSC_IN") (class "Default")
      (node (ref "C40") (pin "1") (pinfunction "61_1") (pintype "passive"))
      (node (ref "MCU1") (pin "12") (pinfunction "PH0_12") (pintype "passive"))
      (node (ref "ZQ1") (pin "1") (pinfunction "10_1") (pintype "passive"))
    )
    (net (code "50") (name "/RCC_OSC_OUT") (class "Default")
      (node (ref "C45") (pin "1") (pinfunction "61_1") (pintype "passive"))
      (node (ref "MCU1") (pin "13") (pinfunction "PH1_13") (pintype "passive"))
      (node (ref "ZQ1") (pin "2") (pinfunction "2_2") (pintype "passive"))
    )
    (net (code "51") (name "/REG_LAT") (class "Default")
      (node (ref "MCU1") (pin "3") (pinfunction "PE4_3") (pintype "passive"))
      (node (ref "U1") (pin "12") (pinfunction "RCLK_12") (pintype "passive"))
    )
    (net (code "52") (name "/RIGHT") (class "Default")
      (node (ref "C5") (pin "2") (pinfunction "62_2") (pintype "passive"))
    )
    (net (code "53") (name "/RTC_INT") (class "Default")
      (node (ref "MCU1") (pin "91") (pinfunction "PB5_91") (pintype "passive"))
      (node (ref "RTC1") (pin "3") (pinfunction "SQW/~{INT}_3") (pintype "passive"))
    )
    (net (code "54") (name "/RTC_RES") (class "Default")
      (node (ref "MCU1") (pin "90") (pinfunction "PB4_90") (pintype "passive"))
      (node (ref "RTC1") (pin "4") (pinfunction "RST_4") (pintype "passive"))
    )
    (net (code "55") (name "/SD_CS") (class "Default")
      (node (ref "MCU1") (pin "33") (pinfunction "PC4_33") (pintype "passive"))
      (node (ref "SDC1") (pin "2") (pinfunction "CD-DAT3/CS_2") (pintype "passive"))
    )
    (net (code "56") (name "/SHDWN") (class "Default")
      (node (ref "AU1") (pin "7") (pinfunction "SD_7") (pintype "passive"))
      (node (ref "OC1") (pin "11") (pinfunction "3_11") (pintype "passive"))
      (node (ref "R22") (pin "1") (pinfunction "2_1") (pintype "passive"))
    )
    (net (code "57") (name "/SPI1_MISO") (class "Default")
      (node (ref "MCU1") (pin "31") (pinfunction "PA6_31") (pintype "passive"))
      (node (ref "SDC1") (pin "7") (pinfunction "DAT0/MISO_7") (pintype "passive"))
    )
    (net (code "58") (name "/SPI1_MOSI") (class "Default")
      (node (ref "MCU1") (pin "32") (pinfunction "PA7_32") (pintype "passive"))
      (node (ref "SDC1") (pin "3") (pinfunction "CMD/MOSI_3") (pintype "passive"))
    )
    (net (code "59") (name "/SPI1_SCK") (class "Default")
      (node (ref "MCU1") (pin "30") (pinfunction "PA5_30") (pintype "passive"))
      (node (ref "SDC1") (pin "5") (pinfunction "SCK_5") (pintype "passive"))
    )
    (net (code "60") (name "/SPI4_MOSI") (class "Default")
      (node (ref "DR1") (pin "4") (pinfunction "SDI_4") (pintype "passive"))
      (node (ref "MCU1") (pin "5") (pinfunction "PE6_5") (pintype "passive"))
      (node (ref "U1") (pin "14") (pinfunction "SER_14") (pintype "passive"))
    )
    (net (code "61") (name "/SPI4_SCK") (class "Default")
      (node (ref "DR1") (pin "5") (pinfunction "CLK_5") (pintype "passive"))
      (node (ref "MCU1") (pin "1") (pinfunction "PE2_1") (pintype "passive"))
      (node (ref "U1") (pin "11") (pinfunction "SRCLK_11") (pintype "passive"))
    )
    (net (code "62") (name "/SWCLK") (class "Default")
      (node (ref "MCU1") (pin "76") (pinfunction "PA14_76") (pintype "passive"))
    )
    (net (code "63") (name "/SWDAT") (class "Default")
      (node (ref "MCU1") (pin "72") (pinfunction "PA13_72") (pintype "passive"))
    )
    (net (code "64") (name "/UART_RX") (class "Default")
      (node (ref "MCU1") (pin "38") (pinfunction "PE7_38") (pintype "passive"))
    )
    (net (code "65") (name "/UART_TX") (class "Default")
      (node (ref "MCU1") (pin "39") (pinfunction "PE8_39") (pintype "passive"))
    )
    (net (code "66") (name "/UP{slash}DN") (class "Default")
      (node (ref "AU1") (pin "6") (pinfunction "U/D_6") (pintype "passive"))
      (node (ref "OC1") (pin "15") (pinfunction "3_15") (pintype "passive"))
      (node (ref "R13") (pin "1") (pinfunction "2_1") (pintype "passive"))
    )
    (net (code "67") (name "/USB_D+") (class "Default")
      (node (ref "MCU1") (pin "71") (pinfunction "PA12_71") (pintype "passive"))
      (node (ref "UP1") (pin "3") (pinfunction "D_+_3") (pintype "passive"))
    )
    (net (code "68") (name "/USB_D-") (class "Default")
      (node (ref "MCU1") (pin "70") (pinfunction "PA11_70") (pintype "passive"))
      (node (ref "UP1") (pin "2") (pinfunction "D_-_2") (pintype "passive"))
    )
    (net (code "69") (name "/V+") (class "Default")
      (node (ref "C6") (pin "1") (pinfunction "61_1") (pintype "passive"))
      (node (ref "MCU1") (pin "54") (pinfunction "PB15_54") (pintype "passive"))
      (node (ref "SW3") (pin "3") (pinfunction "Q2_3") (pintype "passive"))
      (node (ref "SW3") (pin "4") (pinfunction "Q2_4") (pintype "passive"))
    )
    (net (code "70") (name "/V-") (class "Default")
      (node (ref "C1") (pin "1") (pinfunction "61_1") (pintype "passive"))
      (node (ref "MCU1") (pin "53") (pinfunction "PB14_53") (pintype "passive"))
      (node (ref "SW1") (pin "3") (pinfunction "Q2_3") (pintype "passive"))
      (node (ref "SW1") (pin "4") (pinfunction "Q2_4") (pintype "passive"))
    )
    (net (code "71") (name "/VCI") (class "Default")
      (node (ref "DIS1") (pin "4") (pinfunction "VCI_4") (pintype "passive"))
      (node (ref "R11") (pin "2") (pinfunction "2_2") (pintype "passive"))
    )
    (net (code "72") (name "/V_CLK") (class "Default")
      (node (ref "AU1") (pin "4") (pinfunction "CLK_4") (pintype "passive"))
      (node (ref "OC1") (pin "13") (pinfunction "3_13") (pintype "passive"))
      (node (ref "R18") (pin "1") (pinfunction "2_1") (pintype "passive"))
    )
    (net (code "73") (name "AGND") (class "Default")
      (node (ref "AU1") (pin "5") (pinfunction "GND_5") (pintype "passive"))
      (node (ref "AU2") (pin "3") (pinfunction "CPGND_3") (pintype "passive"))
      (node (ref "AU2") (pin "9") (pinfunction "AGND_9") (pintype "passive"))
      (node (ref "BF1") (pin "1") (pintype "passive"))
      (node (ref "C11") (pin "1") (pinfunction "61_1") (pintype "passive"))
      (node (ref "C12") (pin "2") (pinfunction "62_2") (pintype "passive"))
      (node (ref "C14") (pin "1") (pinfunction "61_1") (pintype "passive"))
      (node (ref "C16") (pin "2") (pinfunction "62_2") (pintype "passive"))
      (node (ref "C17") (pin "1") (pinfunction "61_1") (pintype "passive"))
      (node (ref "C22") (pin "2") (pinfunction "62_2") (pintype "passive"))
      (node (ref "C23") (pin "2") (pinfunction "62_2") (pintype "passive"))
      (node (ref "C26") (pin "1") (pinfunction "61_1") (pintype "passive"))
      (node (ref "C38") (pin "1") (pinfunction "61_1") (pintype "passive"))
      (node (ref "C39") (pin "2") (pinfunction "62_2") (pintype "passive"))
      (node (ref "C41") (pin "2") (pinfunction "62_2") (pintype "passive"))
      (node (ref "C51") (pin "1") (pinfunction "61_1") (pintype "passive"))
      (node (ref "C52") (pin "1") (pinfunction "61_1") (pintype "passive"))
      (node (ref "LED2") (pin "1") (pinfunction "5_1") (pintype "passive"))
      (node (ref "R13") (pin "2") (pinfunction "2_2") (pintype "passive"))
      (node (ref "R16") (pin "1") (pinfunction "2_1") (pintype "passive"))
      (node (ref "R18") (pin "2") (pinfunction "2_2") (pintype "passive"))
      (node (ref "R22") (pin "2") (pinfunction "2_2") (pintype "passive"))
      (node (ref "R3") (pin "2") (pinfunction "2_2") (pintype "passive"))
      (node (ref "SB12") (pin "1") (pintype "passive"))
      (node (ref "SB13") (pin "2") (pintype "passive"))
      (node (ref "U2") (pin "4") (pinfunction "-_4") (pintype "passive"))
      (node (ref "U3") (pin "3") (pinfunction "G_3") (pintype "passive"))
    )
    (net (code "74") (name "DGND") (class "Default")
      (node (ref "AU2") (pin "19") (pinfunction "GND_19") (pintype "passive"))
      (node (ref "C1") (pin "2") (pinfunction "62_2") (pintype "passive"))
      (node (ref "C10") (pin "1") (pinfunction "61_1") (pintype "passive"))
      (node (ref "C13") (pin "2") (pinfunction "62_2") (pintype "passive"))
      (node (ref "C18") (pin "2") (pinfunction "62_2") (pintype "passive"))
      (node (ref "C19") (pin "2") (pinfunction "62_2") (pintype "passive"))
      (node (ref "C2") (pin "2") (pinfunction "62_2") (pintype "passive"))
      (node (ref "C20") (pin "1") (pinfunction "61_1") (pintype "passive"))
      (node (ref "C24") (pin "1") (pinfunction "61_1") (pintype "passive"))
      (node (ref "C25") (pin "2") (pinfunction "62_2") (pintype "passive"))
      (node (ref "C27") (pin "2") (pinfunction "62_2") (pintype "passive"))
      (node (ref "C28") (pin "2") (pinfunction "62_2") (pintype "passive"))
      (node (ref "C29") (pin "1") (pinfunction "61_1") (pintype "passive"))
      (node (ref "C3") (pin "2") (pinfunction "62_2") (pintype "passive"))
      (node (ref "C30") (pin "1") (pinfunction "61_1") (pintype "passive"))
      (node (ref "C31") (pin "1") (pinfunction "61_1") (pintype "passive"))
      (node (ref "C32") (pin "1") (pinfunction "61_1") (pintype "passive"))
      (node (ref "C33") (pin "1") (pinfunction "61_1") (pintype "passive"))
      (node (ref "C34") (pin "1") (pinfunction "61_1") (pintype "passive"))
      (node (ref "C36") (pin "2") (pinfunction "62_2") (pintype "passive"))
      (node (ref "C37") (pin "1") (pinfunction "61_1") (pintype "passive"))
      (node (ref "C40") (pin "2") (pinfunction "62_2") (pintype "passive"))
      (node (ref "C42") (pin "1") (pinfunction "61_1") (pintype "passive"))
      (node (ref "C43") (pin "2") (pinfunction "62_2") (pintype "passive"))
      (node (ref "C44") (pin "1") (pinfunction "61_1") (pintype "passive"))
      (node (ref "C45") (pin "2") (pinfunction "62_2") (pintype "passive"))
      (node (ref "C46") (pin "1") (pinfunction "61_1") (pintype "passive"))
      (node (ref "C47") (pin "1") (pinfunction "61_1") (pintype "passive"))
      (node (ref "C48") (pin "1") (pinfunction "61_1") (pintype "passive"))
      (node (ref "C50") (pin "2") (pinfunction "62_2") (pintype "passive"))
      (node (ref "C53") (pin "1") (pinfunction "61_1") (pintype "passive"))
      (node (ref "C54") (pin "1") (pinfunction "61_1") (pintype "passive"))
      (node (ref "C55") (pin "1") (pinfunction "61_1") (pintype "passive"))
      (node (ref "C56") (pin "1") (pinfunction "61_1") (pintype "passive"))
      (node (ref "C57") (pin "1") (pinfunction "61_1") (pintype "passive"))
      (node (ref "C58") (pin "1") (pinfunction "61_1") (pintype "passive"))
      (node (ref "C59") (pin "1") (pinfunction "61_1") (pintype "passive"))
      (node (ref "C6") (pin "2") (pinfunction "62_2") (pintype "passive"))
      (node (ref "C61") (pin "2") (pinfunction "62_2") (pintype "passive"))
      (node (ref "C7") (pin "2") (pinfunction "62_2") (pintype "passive"))
      (node (ref "CHC1") (pin "3") (pinfunction "VSS_3") (pintype "passive"))
      (node (ref "CHC1") (pin "7") (pinfunction "ISET2_7") (pintype "passive"))
      (node (ref "DIS1") (pin "20") (pinfunction "GND_20") (pintype "passive"))
      (node (ref "DIS1") (pin "3") (pinfunction "GND_3") (pintype "passive"))
      (node (ref "DR1") (pin "2") (pinfunction "GND_2") (pintype "passive"))
      (node (ref "DR1") (pin "7") (pinfunction "W_7") (pintype "passive"))
      (node (ref "GA1") (pin "2") (pinfunction "+_2") (pintype "passive"))
      (node (ref "GB1") (pin "1") (pinfunction "+_1") (pintype "passive"))
      (node (ref "LED3") (pin "2") (pinfunction "6_2") (pintype "passive"))
      (node (ref "LED4") (pin "2") (pinfunction "6_2") (pintype "passive"))
      (node (ref "MCU1") (pin "10") (pinfunction "VSS_10") (pintype "passive"))
      (node (ref "MCU1") (pin "20") (pinfunction "VSSA_20") (pintype "passive"))
      (node (ref "MCU1") (pin "27") (pinfunction "VSS_27") (pintype "passive"))
      (node (ref "MCU1") (pin "74") (pinfunction "VSS_74") (pintype "passive"))
      (node (ref "MCU1") (pin "99") (pinfunction "VSS_99") (pintype "passive"))
      (node (ref "PS1") (pin "1") (pinfunction "ADJ_1") (pintype "passive"))
      (node (ref "R11") (pin "1") (pinfunction "1_1") (pintype "passive"))
      (node (ref "R12") (pin "1") (pinfunction "2_1") (pintype "passive"))
      (node (ref "R17") (pin "1") (pinfunction "2_1") (pintype "passive"))
      (node (ref "R21") (pin "1") (pinfunction "2_1") (pintype "passive"))
      (node (ref "R26") (pin "1") (pinfunction "2_1") (pintype "passive"))
      (node (ref "R30") (pin "1") (pinfunction "2_1") (pintype "passive"))
      (node (ref "R31") (pin "1") (pinfunction "2_1") (pintype "passive"))
      (node (ref "R32") (pin "2") (pinfunction "2_2") (pintype "passive"))
      (node (ref "R9") (pin "2") (pinfunction "2_2") (pintype "passive"))
      (node (ref "RTC1") (pin "13") (pinfunction "GND_13") (pintype "passive"))
      (node (ref "SB13") (pin "1") (pintype "passive"))
      (node (ref "SDC1") (pin "6") (pinfunction "GND_6") (pintype "passive"))
      (node (ref "SW1") (pin "1") (pinfunction "Q1_1") (pintype "passive"))
      (node (ref "SW1") (pin "2") (pinfunction "Q1_2") (pintype "passive"))
      (node (ref "SW2") (pin "1") (pinfunction "Q1_1") (pintype "passive"))
      (node (ref "SW2") (pin "2") (pinfunction "Q1_2") (pintype "passive"))
      (node (ref "SW3") (pin "1") (pinfunction "Q1_1") (pintype "passive"))
      (node (ref "SW3") (pin "2") (pinfunction "Q1_2") (pintype "passive"))
      (node (ref "SW4") (pin "1") (pinfunction "Q1_1") (pintype "passive"))
      (node (ref "SW4") (pin "2") (pinfunction "Q1_2") (pintype "passive"))
      (node (ref "SW5") (pin "1") (pinfunction "Q1_1") (pintype "passive"))
      (node (ref "SW5") (pin "2") (pinfunction "Q1_2") (pintype "passive"))
      (node (ref "SW7") (pin "1") (pinfunction "Q1_1") (pintype "passive"))
      (node (ref "SW7") (pin "2") (pinfunction "Q1_2") (pintype "passive"))
      (node (ref "U1") (pin "13") (pinfunction "OE_13") (pintype "passive"))
      (node (ref "U1") (pin "8") (pinfunction "GND_8") (pintype "passive"))
      (node (ref "UP1") (pin "4") (pinfunction "GND_4") (pintype "passive"))
      (node (ref "UP1") (pin "5") (pinfunction "GND_5") (pintype "passive"))
    )
    (net (code "75") (name "Net-(AU1-BYPASS)") (class "Default")
      (node (ref "AU1") (pin "3") (pinfunction "BYPASS_3") (pintype "passive"))
      (node (ref "C11") (pin "2") (pinfunction "62_2") (pintype "passive"))
    )
    (net (code "76") (name "Net-(AU1-VDD)") (class "Default")
      (node (ref "AU1") (pin "10") (pinfunction "VDD_10") (pintype "passive"))
      (node (ref "SB3") (pin "1") (pintype "passive"))
    )
    (net (code "77") (name "Net-(AU1-VIN1)") (class "Default")
      (node (ref "AU1") (pin "2") (pinfunction "VIN1_2") (pintype "passive"))
      (node (ref "C8") (pin "1") (pinfunction "61_1") (pintype "passive"))
    )
    (net (code "78") (name "Net-(AU1-VIN2)") (class "Default")
      (node (ref "AU1") (pin "8") (pinfunction "VIN2_8") (pintype "passive"))
      (node (ref "C9") (pin "1") (pinfunction "61_1") (pintype "passive"))
    )
    (net (code "79") (name "Net-(AU1-VOUT1)") (class "Default")
      (node (ref "AU1") (pin "1") (pinfunction "VOUT1_1") (pintype "passive"))
      (node (ref "C4") (pin "1") (pinfunction "61_1") (pintype "passive"))
    )
    (net (code "80") (name "Net-(AU1-VOUT2)") (class "Default")
      (node (ref "AU1") (pin "9") (pinfunction "VOUT2_9") (pintype "passive"))
      (node (ref "C5") (pin "1") (pinfunction "61_1") (pintype "passive"))
    )
    (net (code "81") (name "Net-(AU2-CAPM)") (class "Default")
      (node (ref "AU2") (pin "4") (pinfunction "CAPM_4") (pintype "passive"))
      (node (ref "C35") (pin "2") (pinfunction "62_2") (pintype "passive"))
    )
    (net (code "82") (name "Net-(AU2-CAPP)") (class "Default")
      (node (ref "AU2") (pin "2") (pinfunction "CAPP_2") (pintype "passive"))
      (node (ref "C35") (pin "1") (pinfunction "61_1") (pintype "passive"))
    )
    (net (code "83") (name "Net-(AU2-LDOO)") (class "Default")
      (node (ref "AU2") (pin "18") (pinfunction "LDOO_18") (pintype "passive"))
      (node (ref "C42") (pin "2") (pinfunction "62_2") (pintype "passive"))
      (node (ref "C43") (pin "1") (pinfunction "61_1") (pintype "passive"))
    )
    (net (code "84") (name "Net-(AU2-OUTL)") (class "Default")
      (node (ref "AU2") (pin "6") (pinfunction "OUTL_6") (pintype "passive"))
      (node (ref "R27") (pin "2") (pinfunction "2_2") (pintype "passive"))
    )
    (net (code "85") (name "Net-(AU2-OUTR)") (class "Default")
      (node (ref "AU2") (pin "7") (pinfunction "OUTR_7") (pintype "passive"))
      (node (ref "R29") (pin "2") (pinfunction "2_2") (pintype "passive"))
    )
    (net (code "86") (name "Net-(AU2-VDD)") (class "Default")
      (node (ref "AU2") (pin "20") (pinfunction "VDD_20") (pintype "passive"))
      (node (ref "SB7") (pin "1") (pintype "passive"))
    )
    (net (code "87") (name "Net-(AU2-VNEG)") (class "Default")
      (node (ref "AU2") (pin "5") (pinfunction "VNEG_5") (pintype "passive"))
      (node (ref "C39") (pin "1") (pinfunction "61_1") (pintype "passive"))
    )
    (net (code "88") (name "Net-(C20-62)") (class "Default")
      (node (ref "C20") (pin "2") (pinfunction "62_2") (pintype "passive"))
      (node (ref "MCU1") (pin "73") (pinfunction "VCAP2_73") (pintype "passive"))
    )
    (net (code "89") (name "Net-(C21-61)") (class "Default")
      (node (ref "C21") (pin "1") (pinfunction "61_1") (pintype "passive"))
      (node (ref "R19") (pin "2") (pinfunction "2_2") (pintype "passive"))
    )
    (net (code "90") (name "Net-(C21-62)") (class "Default")
      (node (ref "BF1") (pin "2") (pintype "passive"))
      (node (ref "C21") (pin "2") (pinfunction "62_2") (pintype "passive"))
      (node (ref "R14") (pin "1") (pinfunction "2_1") (pintype "passive"))
    )
    (net (code "91") (name "Net-(C22-61)") (class "Default")
      (node (ref "C22") (pin "1") (pinfunction "61_1") (pintype "passive"))
      (node (ref "R15") (pin "1") (pinfunction "2_1") (pintype "passive"))
      (node (ref "R16") (pin "2") (pinfunction "2_2") (pintype "passive"))
      (node (ref "U2") (pin "3") (pintype "passive"))
    )
    (net (code "92") (name "Net-(C37-62)") (class "Default")
      (node (ref "C37") (pin "2") (pinfunction "62_2") (pintype "passive"))
      (node (ref "MCU1") (pin "49") (pinfunction "VCAP1_49") (pintype "passive"))
    )
    (net (code "93") (name "Net-(C49-61)") (class "Default")
      (node (ref "C49") (pin "1") (pinfunction "61_1") (pintype "passive"))
      (node (ref "SB9") (pin "1") (pintype "passive"))
      (node (ref "ZQ2") (pin "1") (pinfunction "10_1") (pintype "passive"))
    )
    (net (code "94") (name "Net-(C49-62)") (class "Default")
      (node (ref "C49") (pin "2") (pinfunction "62_2") (pintype "passive"))
      (node (ref "C60") (pin "2") (pinfunction "62_2") (pintype "passive"))
      (node (ref "SB12") (pin "2") (pintype "passive"))
    )
    (net (code "95") (name "Net-(CHC1-ISET)") (class "Default")
      (node (ref "CHC1") (pin "2") (pinfunction "ISET_2") (pintype "passive"))
      (node (ref "R31") (pin "2") (pinfunction "2_2") (pintype "passive"))
    )
    (net (code "96") (name "Net-(CHC1-PTRM)") (class "Default")
      (node (ref "CHC1") (pin "4") (pinfunction "PTRM_4") (pintype "passive"))
      (node (ref "R32") (pin "1") (pinfunction "2_1") (pintype "passive"))
    )
    (net (code "97") (name "Net-(CHC1-TS)") (class "Default")
      (node (ref "CHC1") (pin "9") (pinfunction "TS_9") (pintype "passive"))
      (node (ref "R30") (pin "2") (pinfunction "2_2") (pintype "passive"))
    )
    (net (code "98") (name "Net-(DIS1-DB0)") (class "Default")
      (node (ref "DIS1") (pin "19") (pinfunction "DB0_19") (pintype "passive"))
      (node (ref "U1") (pin "7") (pinfunction "Q7_7") (pintype "passive"))
    )
    (net (code "99") (name "Net-(DIS1-DB1)") (class "Default")
      (node (ref "DIS1") (pin "18") (pinfunction "DB1_18") (pintype "passive"))
      (node (ref "U1") (pin "6") (pinfunction "Q6_6") (pintype "passive"))
    )
    (net (code "100") (name "Net-(DIS1-DB2)") (class "Default")
      (node (ref "DIS1") (pin "17") (pinfunction "DB2_17") (pintype "passive"))
      (node (ref "U1") (pin "5") (pinfunction "Q5_5") (pintype "passive"))
    )
    (net (code "101") (name "Net-(DIS1-DB3)") (class "Default")
      (node (ref "DIS1") (pin "16") (pinfunction "DB3_16") (pintype "passive"))
      (node (ref "U1") (pin "4") (pinfunction "Q4_4") (pintype "passive"))
    )
    (net (code "102") (name "Net-(DIS1-DB4)") (class "Default")
      (node (ref "DIS1") (pin "15") (pinfunction "DB4_15") (pintype "passive"))
      (node (ref "U1") (pin "3") (pinfunction "Q3_3") (pintype "passive"))
    )
    (net (code "103") (name "Net-(DIS1-DB5)") (class "Default")
      (node (ref "DIS1") (pin "14") (pinfunction "DB5_14") (pintype "passive"))
      (node (ref "U1") (pin "2") (pinfunction "Q2_2") (pintype "passive"))
    )
    (net (code "104") (name "Net-(DIS1-DB6)") (class "Default")
      (node (ref "DIS1") (pin "13") (pinfunction "DB6_13") (pintype "passive"))
      (node (ref "U1") (pin "1") (pinfunction "Q1_1") (pintype "passive"))
    )
    (net (code "105") (name "Net-(DIS1-DB7)") (class "Default")
      (node (ref "DIS1") (pin "12") (pinfunction "DB7_12") (pintype "passive"))
      (node (ref "U1") (pin "15") (pinfunction "Q0_15") (pintype "passive"))
    )
    (net (code "106") (name "Net-(DIS1-LEDA)") (class "Default")
      (node (ref "DIS1") (pin "2") (pinfunction "LEDA_2") (pintype "passive"))
      (node (ref "VT1") (pin "2") (pinfunction "D_2") (pintype "passive"))
    )
    (net (code "107") (name "Net-(DIS1-LEDK)") (class "Default")
      (node (ref "DIS1") (pin "1") (pinfunction "LEDK_1") (pintype "passive"))
      (node (ref "SB1") (pin "2") (pintype "passive"))
    )
    (net (code "108") (name "Net-(DR1-Pad1)") (class "Default")
      (node (ref "DR1") (pin "1") (pintype "passive"))
      (node (ref "SB1") (pin "1") (pintype "passive"))
    )
    (net (code "109") (name "Net-(LED1-B)") (class "Default")
      (node (ref "LED1") (pin "4") (pinfunction "B_4") (pintype "passive"))
      (node (ref "R6") (pin "1") (pinfunction "2_1") (pintype "passive"))
    )
    (net (code "110") (name "Net-(LED1-G)") (class "Default")
      (node (ref "LED1") (pin "2") (pinfunction "G_2") (pintype "passive"))
      (node (ref "R8") (pin "2") (pinfunction "2_2") (pintype "passive"))
    )
    (net (code "111") (name "Net-(LED1-R)") (class "Default")
      (node (ref "LED1") (pin "3") (pinfunction "R_3") (pintype "passive"))
      (node (ref "R7") (pin "1") (pinfunction "2_1") (pintype "passive"))
    )
    (net (code "112") (name "Net-(LED2-6)") (class "Default")
      (node (ref "LED2") (pin "2") (pinfunction "6_2") (pintype "passive"))
      (node (ref "R10") (pin "1") (pinfunction "2_1") (pintype "passive"))
    )
    (net (code "113") (name "Net-(LED3-5)") (class "Default")
      (node (ref "LED3") (pin "1") (pinfunction "5_1") (pintype "passive"))
      (node (ref "R20") (pin "2") (pinfunction "2_2") (pintype "passive"))
    )
    (net (code "114") (name "Net-(LED4-5)") (class "Default")
      (node (ref "LED4") (pin "1") (pinfunction "5_1") (pintype "passive"))
      (node (ref "R23") (pin "2") (pinfunction "2_2") (pintype "passive"))
    )
    (net (code "115") (name "Net-(MCU1-BOOT0)") (class "Default")
      (node (ref "MCU1") (pin "94") (pinfunction "BOOT0_94") (pintype "passive"))
      (node (ref "R9") (pin "1") (pinfunction "2_1") (pintype "passive"))
    )
    (net (code "116") (name "Net-(OC1-Pad2)") (class "Default")
      (node (ref "OC1") (pin "2") (pinfunction "2_2") (pintype "passive"))
      (node (ref "R12") (pin "2") (pinfunction "2_2") (pintype "passive"))
    )
    (net (code "117") (name "Net-(OC1B-2)") (class "Default")
      (node (ref "OC1") (pin "4") (pinfunction "2_4") (pintype "passive"))
      (node (ref "R17") (pin "2") (pinfunction "2_2") (pintype "passive"))
    )
    (net (code "118") (name "Net-(OC1C-2)") (class "Default")
      (node (ref "OC1") (pin "6") (pinfunction "2_6") (pintype "passive"))
      (node (ref "R21") (pin "2") (pinfunction "2_2") (pintype "passive"))
    )
    (net (code "119") (name "Net-(OC1D-2)") (class "Default")
      (node (ref "OC1") (pin "8") (pinfunction "2_8") (pintype "passive"))
      (node (ref "R4") (pin "2") (pinfunction "2_2") (pintype "passive"))
    )
    (net (code "120") (name "Net-(PS1-IN)") (class "Default")
      (node (ref "PS1") (pin "3") (pinfunction "IN_3") (pintype "passive"))
      (node (ref "SB8") (pin "2") (pintype "passive"))
    )
    (net (code "121") (name "Net-(R4-2-Pad1)") (class "Default")
      (node (ref "R4") (pin "1") (pinfunction "2_1") (pintype "passive"))
      (node (ref "SB2") (pin "1") (pintype "passive"))
    )
    (net (code "122") (name "Net-(R19-2-Pad1)") (class "Default")
      (node (ref "R19") (pin "1") (pinfunction "2_1") (pintype "passive"))
      (node (ref "R24") (pin "1") (pinfunction "1_1") (pintype "passive"))
      (node (ref "U2") (pin "2") (pinfunction "-_2") (pintype "passive"))
    )
    (net (code "123") (name "Net-(R24-Pad2)") (class "Default")
      (node (ref "R24") (pin "2") (pinfunction "2_2") (pintype "passive"))
      (node (ref "R24") (pin "3") (pinfunction "3_3") (pintype "passive"))
      (node (ref "R25") (pin "1") (pinfunction "2_1") (pintype "passive"))
    )
    (net (code "124") (name "Net-(RTC1-32kHz)") (class "Default")
      (node (ref "R5") (pin "2") (pinfunction "2_2") (pintype "passive"))
      (node (ref "RTC1") (pin "1") (pinfunction "32kHz_1") (pintype "passive"))
    )
    (net (code "125") (name "Net-(RTC1-VCC)") (class "Default")
      (node (ref "RTC1") (pin "2") (pinfunction "VCC_2") (pintype "passive"))
      (node (ref "SB4") (pin "2") (pintype "passive"))
    )
    (net (code "126") (name "Net-(SDC1-VDD)") (class "Default")
      (node (ref "SB6") (pin "1") (pintype "passive"))
      (node (ref "SDC1") (pin "4") (pinfunction "VDD_4") (pintype "passive"))
    )
    (net (code "127") (name "Net-(U2A-+)") (class "Default")
      (node (ref "SB5") (pin "1") (pintype "passive"))
      (node (ref "U2") (pin "8") (pinfunction "+_8") (pintype "passive"))
    )
    (net (code "128") (name "Net-(U3-X)") (class "Default")
      (node (ref "SB9") (pin "2") (pintype "passive"))
      (node (ref "U3") (pin "2") (pinfunction "X_2") (pintype "passive"))
    )
    (net (code "129") (name "unconnected-(CHC1-NC.-Pad6)") (class "Default")
      (node (ref "CHC1") (pin "6") (pinfunction "NC._6") (pintype "passive+no_connect"))
    )
    (net (code "130") (name "unconnected-(DIS1-NC.-Pad6)") (class "Default")
      (node (ref "DIS1") (pin "6") (pinfunction "NC._6") (pintype "passive+no_connect"))
    )
    (net (code "131") (name "unconnected-(DIS1-NC.-Pad21)") (class "Default")
      (node (ref "DIS1") (pin "21") (pinfunction "NC._21") (pintype "passive+no_connect"))
    )
    (net (code "132") (name "unconnected-(DIS1-NC.-Pad22)") (class "Default")
      (node (ref "DIS1") (pin "22") (pinfunction "NC._22") (pintype "passive+no_connect"))
    )
    (net (code "133") (name "unconnected-(DIS1-NC.-Pad23)") (class "Default")
      (node (ref "DIS1") (pin "23") (pinfunction "NC._23") (pintype "passive+no_connect"))
    )
    (net (code "134") (name "unconnected-(DIS1-NC.-Pad24)") (class "Default")
      (node (ref "DIS1") (pin "24") (pinfunction "NC._24") (pintype "passive+no_connect"))
    )
    (net (code "135") (name "unconnected-(DR1-Pad8)") (class "Default")
      (node (ref "DR1") (pin "8") (pintype "passive+no_connect"))
    )
    (net (code "136") (name "unconnected-(MCU1-PA2-Pad25)") (class "Default")
      (node (ref "MCU1") (pin "25") (pinfunction "PA2_25") (pintype "passive+no_connect"))
    )
    (net (code "137") (name "unconnected-(MCU1-PA3-Pad26)") (class "Default")
      (node (ref "MCU1") (pin "26") (pinfunction "PA3_26") (pintype "passive+no_connect"))
    )
    (net (code "138") (name "unconnected-(MCU1-PA8-Pad67)") (class "Default")
      (node (ref "MCU1") (pin "67") (pinfunction "PA8_67") (pintype "passive+no_connect"))
    )
    (net (code "139") (name "unconnected-(MCU1-PA9-Pad68)") (class "Default")
      (node (ref "MCU1") (pin "68") (pinfunction "PA9_68") (pintype "passive+no_connect"))
    )
    (net (code "140") (name "unconnected-(MCU1-PA10-Pad69)") (class "Default")
      (node (ref "MCU1") (pin "69") (pinfunction "PA10_69") (pintype "passive+no_connect"))
    )
    (net (code "141") (name "unconnected-(MCU1-PB2-Pad37)") (class "Default")
      (node (ref "MCU1") (pin "37") (pinfunction "PB2_37") (pintype "passive+no_connect"))
    )
    (net (code "142") (name "unconnected-(MCU1-PB3-Pad89)") (class "Default")
      (node (ref "MCU1") (pin "89") (pinfunction "PB3_89") (pintype "passive+no_connect"))
    )
    (net (code "143") (name "unconnected-(MCU1-PB10-Pad47)") (class "Default")
      (node (ref "MCU1") (pin "47") (pinfunction "PB10_47") (pintype "passive+no_connect"))
    )
    (net (code "144") (name "unconnected-(MCU1-PB11-Pad48)") (class "Default")
      (node (ref "MCU1") (pin "48") (pinfunction "PB11_48") (pintype "passive+no_connect"))
    )
    (net (code "145") (name "unconnected-(MCU1-PC0-Pad15)") (class "Default")
      (node (ref "MCU1") (pin "15") (pinfunction "PC0_15") (pintype "passive+no_connect"))
    )
    (net (code "146") (name "unconnected-(MCU1-PC1-Pad16)") (class "Default")
      (node (ref "MCU1") (pin "16") (pinfunction "PC1_16") (pintype "passive+no_connect"))
    )
    (net (code "147") (name "unconnected-(MCU1-PC2-Pad17)") (class "Default")
      (node (ref "MCU1") (pin "17") (pinfunction "PC2_17") (pintype "passive+no_connect"))
    )
    (net (code "148") (name "unconnected-(MCU1-PC3-Pad18)") (class "Default")
      (node (ref "MCU1") (pin "18") (pinfunction "PC3_18") (pintype "passive+no_connect"))
    )
    (net (code "149") (name "unconnected-(MCU1-PD3-Pad84)") (class "Default")
      (node (ref "MCU1") (pin "84") (pinfunction "PD3_84") (pintype "passive+no_connect"))
    )
    (net (code "150") (name "unconnected-(MCU1-PD4-Pad85)") (class "Default")
      (node (ref "MCU1") (pin "85") (pinfunction "PD4_85") (pintype "passive+no_connect"))
    )
    (net (code "151") (name "unconnected-(MCU1-PD5-Pad86)") (class "Default")
      (node (ref "MCU1") (pin "86") (pinfunction "PD5_86") (pintype "passive+no_connect"))
    )
    (net (code "152") (name "unconnected-(MCU1-PD6-Pad87)") (class "Default")
      (node (ref "MCU1") (pin "87") (pinfunction "PD6_87") (pintype "passive+no_connect"))
    )
    (net (code "153") (name "unconnected-(MCU1-PD7-Pad88)") (class "Default")
      (node (ref "MCU1") (pin "88") (pinfunction "PD7_88") (pintype "passive+no_connect"))
    )
    (net (code "154") (name "unconnected-(MCU1-PD9-Pad56)") (class "Default")
      (node (ref "MCU1") (pin "56") (pinfunction "PD9_56") (pintype "passive+no_connect"))
    )
    (net (code "155") (name "unconnected-(MCU1-PD12-Pad59)") (class "Default")
      (node (ref "MCU1") (pin "59") (pinfunction "PD12_59") (pintype "passive+no_connect"))
    )
    (net (code "156") (name "unconnected-(MCU1-PE9-Pad40)") (class "Default")
      (node (ref "MCU1") (pin "40") (pinfunction "PE9_40") (pintype "passive+no_connect"))
    )
    (net (code "157") (name "unconnected-(MCU1-PE10-Pad41)") (class "Default")
      (node (ref "MCU1") (pin "41") (pinfunction "PE10_41") (pintype "passive+no_connect"))
    )
    (net (code "158") (name "unconnected-(MCU1-PE11-Pad42)") (class "Default")
      (node (ref "MCU1") (pin "42") (pinfunction "PE11_42") (pintype "passive+no_connect"))
    )
    (net (code "159") (name "unconnected-(MCU1-PE12-Pad43)") (class "Default")
      (node (ref "MCU1") (pin "43") (pinfunction "PE12_43") (pintype "passive+no_connect"))
    )
    (net (code "160") (name "unconnected-(MCU1-PE13-Pad44)") (class "Default")
      (node (ref "MCU1") (pin "44") (pinfunction "PE13_44") (pintype "passive+no_connect"))
    )
    (net (code "161") (name "unconnected-(MCU1-PE14-Pad45)") (class "Default")
      (node (ref "MCU1") (pin "45") (pinfunction "PE14_45") (pintype "passive+no_connect"))
    )
    (net (code "162") (name "unconnected-(MCU1-PE15-Pad46)") (class "Default")
      (node (ref "MCU1") (pin "46") (pinfunction "PE15_46") (pintype "passive+no_connect"))
    )
    (net (code "163") (name "unconnected-(SDC1-DAT1{slash}X-Pad8)") (class "Default")
      (node (ref "SDC1") (pin "8") (pinfunction "DAT1/X_8") (pintype "passive+no_connect"))
    )
    (net (code "164") (name "unconnected-(SDC1-DAT2{slash}X-Pad1)") (class "Default")
      (node (ref "SDC1") (pin "1") (pinfunction "DAT2/X_1") (pintype "passive+no_connect"))
    )
    (net (code "165") (name "unconnected-(U1-Q7s-Pad9)") (class "Default")
      (node (ref "U1") (pin "9") (pinfunction "Q7s_9") (pintype "passive+no_connect"))
    )
    (net (code "166") (name "unconnected-(U2-Pad5)") (class "Default")
      (node (ref "U2") (pin "5") (pintype "passive+no_connect"))
    )
    (net (code "167") (name "unconnected-(U2-Pad7)") (class "Default")
      (node (ref "U2") (pin "7") (pintype "passive+no_connect"))
    )
    (net (code "168") (name "unconnected-(U2B---Pad6)") (class "Default")
      (node (ref "U2") (pin "6") (pinfunction "-_6") (pintype "passive+no_connect"))
    )
  )
)
